# SensorTile_Breakout.net
KiCad netlist of a schematic drawn in EAGLE
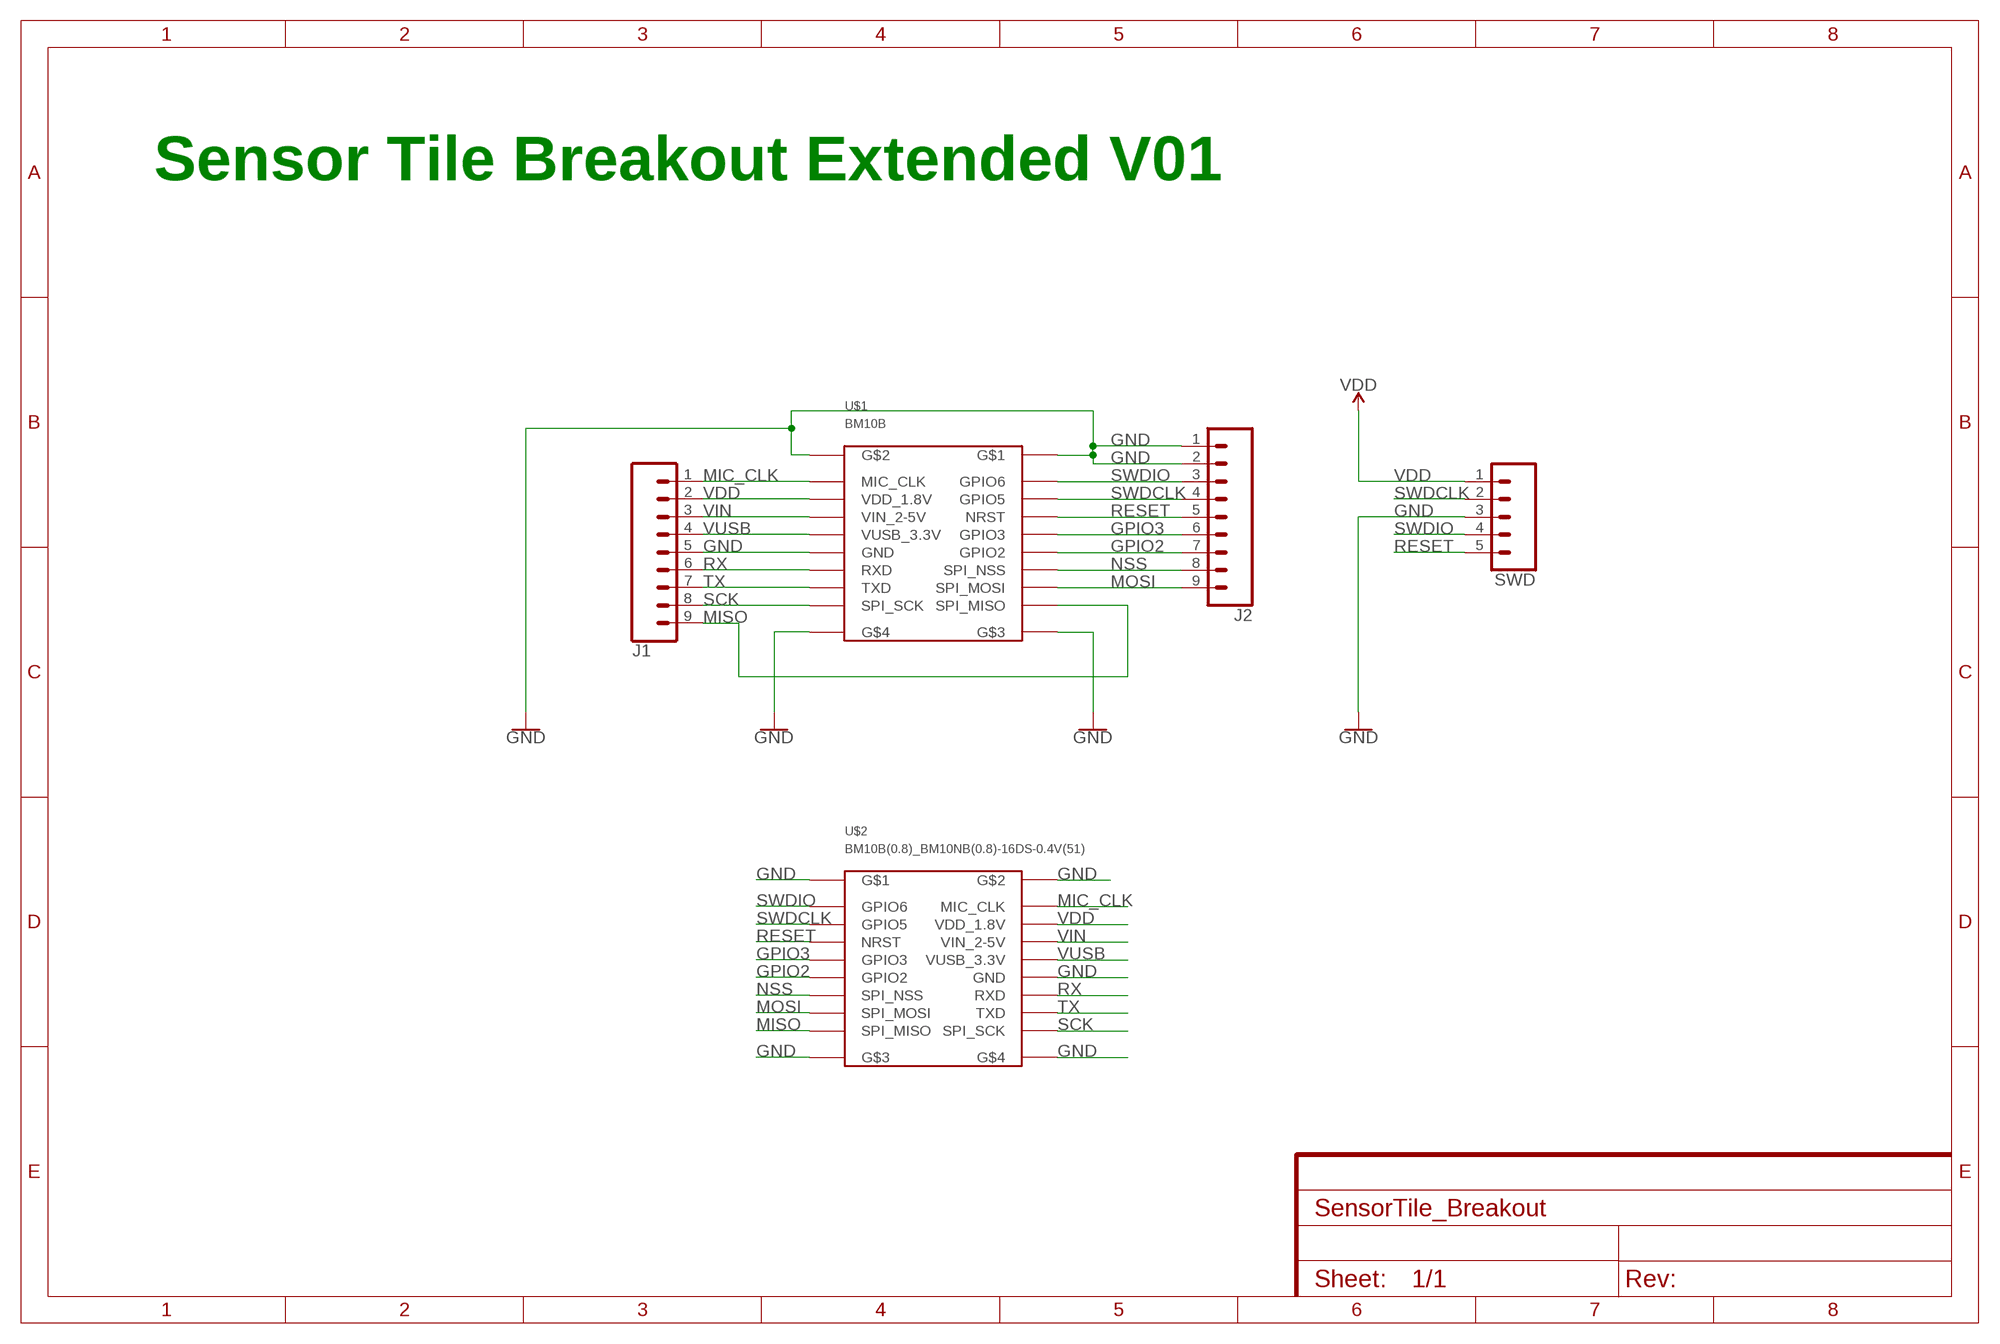
[diagram p0: schematic, sheet 1]

(export (version "E")
  (design (tool "Eeschema 10.0.6"))
  (components
    (comp (ref "J1")
      (value "CONN_09")
      (footprint "eagle-import:1X09")
      (libsource (lib "eagle-import") (part "CONN_09"))
    )
    (comp (ref "J2")
      (value "CONN_09")
      (footprint "eagle-import:1X09")
      (libsource (lib "eagle-import") (part "CONN_09"))
    )
    (comp (ref "SWD")
      (value "CONN_05")
      (footprint "eagle-import:1X05")
      (libsource (lib "eagle-import") (part "CONN_05"))
    )
    (comp (ref "U$1")
      (value "BM10B")
      (footprint "eagle-import:BM10B(0.8)-16DP-0.4V(51)")
      (libsource (lib "eagle-import") (part "BM10B(0.8)-16DP-0.4V(51)"))
    )
    (comp (ref "U$2")
      (value "BM10B(0.8)_BM10NB(0.8)-16DS-0.4V(51)")
      (footprint "eagle-import:BM10B(0.8)_BM10NB(0.8)-16DS-0.4V(51)")
      (libsource (lib "eagle-import") (part "BM10B(0.8)_BM10NB(0.8)-16DS-0.4V(51)"))
    )
  )
  (nets
    (net (code "1") (name "/GPIO2") (class "Default")
      (node (ref "J2") (pin "7") (pinfunction "7_7") (pintype "passive"))
      (node (ref "U$1") (pin "GPIO2") (pinfunction "GPIO2_GPIO2") (pintype "bidirectional"))
      (node (ref "U$2") (pin "GPIO2") (pinfunction "GPIO2_GPIO2") (pintype "bidirectional"))
    )
    (net (code "2") (name "/GPIO3") (class "Default")
      (node (ref "J2") (pin "6") (pinfunction "6_6") (pintype "passive"))
      (node (ref "U$1") (pin "GPIO3") (pinfunction "GPIO3_GPIO3") (pintype "bidirectional"))
      (node (ref "U$2") (pin "GPIO3") (pinfunction "GPIO3_GPIO3") (pintype "bidirectional"))
    )
    (net (code "3") (name "/MIC_CLK") (class "Default")
      (node (ref "J1") (pin "1") (pinfunction "1_1") (pintype "passive"))
      (node (ref "U$1") (pin "MIC_CLK") (pinfunction "MIC_CLK_MIC_CLK") (pintype "bidirectional"))
      (node (ref "U$2") (pin "MIC_CLK") (pinfunction "MIC_CLK_MIC_CLK") (pintype "bidirectional"))
    )
    (net (code "4") (name "/MISO") (class "Default")
      (node (ref "J1") (pin "9") (pinfunction "9_9") (pintype "passive"))
      (node (ref "U$1") (pin "SPI_MISO") (pinfunction "SPI_MISO_SPI_MISO") (pintype "bidirectional"))
      (node (ref "U$2") (pin "SPI_MISO") (pinfunction "SPI_MISO_SPI_MISO") (pintype "bidirectional"))
    )
    (net (code "5") (name "/MOSI") (class "Default")
      (node (ref "J2") (pin "9") (pinfunction "9_9") (pintype "passive"))
      (node (ref "U$1") (pin "SPI_MOSI") (pinfunction "SPI_MOSI_SPI_MOSI") (pintype "bidirectional"))
      (node (ref "U$2") (pin "SPI_MOSI") (pinfunction "SPI_MOSI_SPI_MOSI") (pintype "bidirectional"))
    )
    (net (code "6") (name "/NSS") (class "Default")
      (node (ref "J2") (pin "8") (pinfunction "8_8") (pintype "passive"))
      (node (ref "U$1") (pin "SPI_NSS") (pinfunction "SPI_NSS_SPI_NSS") (pintype "bidirectional"))
      (node (ref "U$2") (pin "SPI_NSS") (pinfunction "SPI_NSS_SPI_NSS") (pintype "bidirectional"))
    )
    (net (code "7") (name "/RESET") (class "Default")
      (node (ref "J2") (pin "5") (pinfunction "5_5") (pintype "passive"))
      (node (ref "SWD") (pin "5") (pinfunction "5_5") (pintype "passive"))
      (node (ref "U$1") (pin "NRST") (pinfunction "NRST_NRST") (pintype "bidirectional"))
      (node (ref "U$2") (pin "NRST") (pinfunction "NRST_NRST") (pintype "bidirectional"))
    )
    (net (code "8") (name "/RX") (class "Default")
      (node (ref "J1") (pin "6") (pinfunction "6_6") (pintype "passive"))
      (node (ref "U$1") (pin "RXD") (pinfunction "RXD_RXD") (pintype "bidirectional"))
      (node (ref "U$2") (pin "RXD") (pinfunction "RXD_RXD") (pintype "bidirectional"))
    )
    (net (code "9") (name "/SCK") (class "Default")
      (node (ref "J1") (pin "8") (pinfunction "8_8") (pintype "passive"))
      (node (ref "U$1") (pin "SPI_SCK") (pinfunction "SPI_SCK_SPI_SCK") (pintype "bidirectional"))
      (node (ref "U$2") (pin "SPI_SCK") (pinfunction "SPI_SCK_SPI_SCK") (pintype "bidirectional"))
    )
    (net (code "10") (name "/SWDCLK") (class "Default")
      (node (ref "J2") (pin "4") (pinfunction "4_4") (pintype "passive"))
      (node (ref "SWD") (pin "2") (pinfunction "2_2") (pintype "passive"))
      (node (ref "U$1") (pin "GPIO5") (pinfunction "GPIO5_GPIO5") (pintype "bidirectional"))
      (node (ref "U$2") (pin "GPIO5") (pinfunction "GPIO5_GPIO5") (pintype "bidirectional"))
    )
    (net (code "11") (name "/SWDIO") (class "Default")
      (node (ref "J2") (pin "3") (pinfunction "3_3") (pintype "passive"))
      (node (ref "SWD") (pin "4") (pinfunction "4_4") (pintype "passive"))
      (node (ref "U$1") (pin "GPIO6") (pinfunction "GPIO6_GPIO6") (pintype "bidirectional"))
      (node (ref "U$2") (pin "GPIO6") (pinfunction "GPIO6_GPIO6") (pintype "bidirectional"))
    )
    (net (code "12") (name "/TX") (class "Default")
      (node (ref "J1") (pin "7") (pinfunction "7_7") (pintype "passive"))
      (node (ref "U$1") (pin "TXD") (pinfunction "TXD_TXD") (pintype "bidirectional"))
      (node (ref "U$2") (pin "TXD") (pinfunction "TXD_TXD") (pintype "bidirectional"))
    )
    (net (code "13") (name "/VIN") (class "Default")
      (node (ref "J1") (pin "3") (pinfunction "3_3") (pintype "passive"))
      (node (ref "U$1") (pin "VIN_2-5V") (pinfunction "VIN_2-5V_VIN_2-5V") (pintype "bidirectional"))
      (node (ref "U$2") (pin "VIN_2-5V") (pinfunction "VIN_2-5V_VIN_2-5V") (pintype "bidirectional"))
    )
    (net (code "14") (name "/VUSB") (class "Default")
      (node (ref "J1") (pin "4") (pinfunction "4_4") (pintype "passive"))
      (node (ref "U$1") (pin "VUSB_3.3V") (pinfunction "VUSB_3.3V_VUSB_3.3V") (pintype "bidirectional"))
      (node (ref "U$2") (pin "VUSB_3.3V") (pinfunction "VUSB_3.3V_VUSB_3.3V") (pintype "bidirectional"))
    )
    (net (code "15") (name "GND") (class "Default")
      (node (ref "J1") (pin "5") (pinfunction "5_5") (pintype "passive"))
      (node (ref "J2") (pin "1") (pinfunction "1_1") (pintype "passive"))
      (node (ref "J2") (pin "2") (pinfunction "2_2") (pintype "passive"))
      (node (ref "SWD") (pin "3") (pinfunction "3_3") (pintype "passive"))
      (node (ref "U$1") (pin "G$1") (pinfunction "G$1_G$1") (pintype "bidirectional"))
      (node (ref "U$1") (pin "G$2") (pinfunction "G$2_G$2") (pintype "bidirectional"))
      (node (ref "U$1") (pin "G$3") (pinfunction "G$3_G$3") (pintype "bidirectional"))
      (node (ref "U$1") (pin "G$4") (pinfunction "G$4_G$4") (pintype "bidirectional"))
      (node (ref "U$1") (pin "GND$1") (pinfunction "GND_GND$1") (pintype "bidirectional"))
      (node (ref "U$2") (pin "G$1") (pinfunction "G$1_G$1") (pintype "bidirectional"))
      (node (ref "U$2") (pin "G$2") (pinfunction "G$2_G$2") (pintype "bidirectional"))
      (node (ref "U$2") (pin "G$3") (pinfunction "G$3_G$3") (pintype "bidirectional"))
      (node (ref "U$2") (pin "G$4") (pinfunction "G$4_G$4") (pintype "bidirectional"))
      (node (ref "U$2") (pin "GND$1") (pinfunction "GND_GND$1") (pintype "bidirectional"))
    )
    (net (code "16") (name "VDD") (class "Default")
      (node (ref "J1") (pin "2") (pinfunction "2_2") (pintype "passive"))
      (node (ref "SWD") (pin "1") (pinfunction "1_1") (pintype "passive"))
      (node (ref "U$1") (pin "VDD_1.8V") (pinfunction "VDD_1.8V_VDD_1.8V") (pintype "bidirectional"))
      (node (ref "U$2") (pin "VDD_1.8V") (pinfunction "VDD_1.8V_VDD_1.8V") (pintype "bidirectional"))
    )
  )
)
